# Compressor.net
KiCad netlist of a schematic drawn in EAGLE
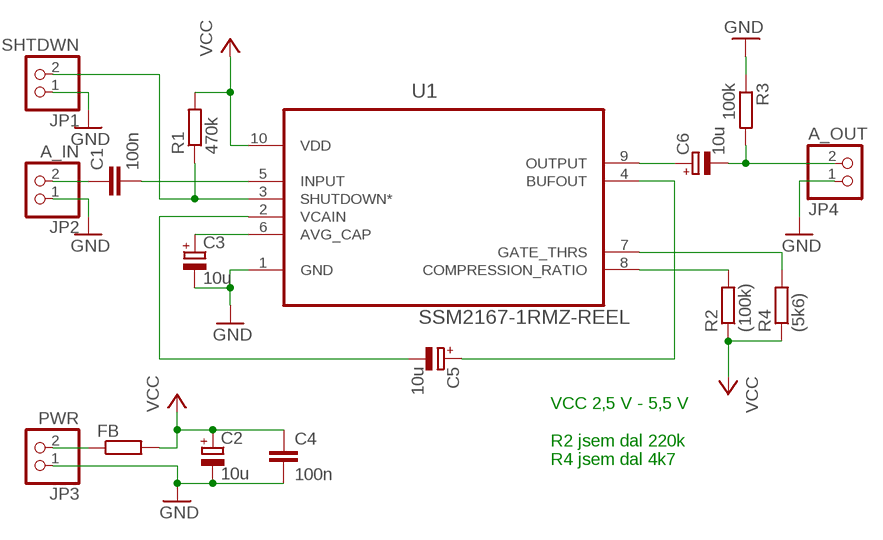
[diagram p0: schematic, sheet 1]

(export (version "E")
  (design (tool "Eeschema 10.0.6"))
  (components
    (comp (ref "C1")
      (value "100n")
      (footprint "eagle-import:C0603")
      (libsource (lib "eagle-import") (part "C-EUC0603"))
    )
    (comp (ref "C2")
      (value "10u")
      (footprint "eagle-import:SMC_A")
      (libsource (lib "eagle-import") (part "CPOL-EUSMCA"))
    )
    (comp (ref "C3")
      (value "10u")
      (footprint "eagle-import:SMC_A")
      (libsource (lib "eagle-import") (part "CPOL-EUSMCA"))
    )
    (comp (ref "C4")
      (value "100n")
      (footprint "eagle-import:C0603")
      (libsource (lib "eagle-import") (part "C-EUC0603"))
    )
    (comp (ref "C5")
      (value "10u")
      (footprint "eagle-import:SMC_A")
      (libsource (lib "eagle-import") (part "CPOL-EUSMCA"))
    )
    (comp (ref "C6")
      (value "10u")
      (footprint "eagle-import:SMC_A")
      (libsource (lib "eagle-import") (part "CPOL-EUSMCA"))
    )
    (comp (ref "FB")
      (value "R-EU_R0603")
      (footprint "eagle-import:R0603")
      (libsource (lib "eagle-import") (part "R-EU_R0603"))
    )
    (comp (ref "JP1")
      (value "SHTDWN")
      (footprint "eagle-import:1X02")
      (libsource (lib "eagle-import") (part "PINHD-1X2"))
    )
    (comp (ref "JP2")
      (value "A_IN")
      (footprint "eagle-import:1X02")
      (libsource (lib "eagle-import") (part "PINHD-1X2"))
    )
    (comp (ref "JP3")
      (value "PWR")
      (footprint "eagle-import:1X02")
      (libsource (lib "eagle-import") (part "PINHD-1X2"))
    )
    (comp (ref "JP4")
      (value "A_OUT")
      (footprint "eagle-import:1X02")
      (libsource (lib "eagle-import") (part "PINHD-1X2"))
    )
    (comp (ref "R1")
      (value "470k")
      (footprint "eagle-import:R0603")
      (libsource (lib "eagle-import") (part "R-EU_R0603"))
    )
    (comp (ref "R2")
      (value "(100k)")
      (footprint "eagle-import:R0603")
      (libsource (lib "eagle-import") (part "R-EU_R0603"))
    )
    (comp (ref "R3")
      (value "100k")
      (footprint "eagle-import:R0603")
      (libsource (lib "eagle-import") (part "R-EU_R0603"))
    )
    (comp (ref "R4")
      (value "(5k6)")
      (footprint "eagle-import:R0603")
      (libsource (lib "eagle-import") (part "R-EU_R0603"))
    )
    (comp (ref "U1")
      (value "SSM2167-1RMZ-REEL")
      (footprint "eagle-import:SOP50P490X110-10N")
      (libsource (lib "eagle-import") (part "SSM2167-1RMZ-REEL"))
    )
  )
  (nets
    (net (code "1") (name "GND") (class "Default")
      (node (ref "C2") (pin "-") (pinfunction "-_-") (pintype "passive"))
      (node (ref "C3") (pin "-") (pinfunction "-_-") (pintype "passive"))
      (node (ref "C4") (pin "2") (pinfunction "2_2") (pintype "passive"))
      (node (ref "JP1") (pin "1") (pinfunction "1_1") (pintype "passive"))
      (node (ref "JP2") (pin "1") (pinfunction "1_1") (pintype "passive"))
      (node (ref "JP3") (pin "1") (pinfunction "1_1") (pintype "passive"))
      (node (ref "JP4") (pin "1") (pinfunction "1_1") (pintype "passive"))
      (node (ref "R3") (pin "1") (pinfunction "1_1") (pintype "passive"))
      (node (ref "U1") (pin "1") (pinfunction "GND_1") (pintype "passive"))
    )
    (net (code "2") (name "Net-(C1-Pad1)") (class "Default")
      (node (ref "C1") (pin "1") (pinfunction "1_1") (pintype "passive"))
      (node (ref "JP2") (pin "2") (pinfunction "2_2") (pintype "passive"))
    )
    (net (code "3") (name "Net-(C6-Pad-)") (class "Default")
      (node (ref "C6") (pin "-") (pinfunction "-_-") (pintype "passive"))
      (node (ref "JP4") (pin "2") (pinfunction "2_2") (pintype "passive"))
      (node (ref "R3") (pin "2") (pinfunction "2_2") (pintype "passive"))
    )
    (net (code "4") (name "Net-(FB-Pad1)") (class "Default")
      (node (ref "FB") (pin "1") (pinfunction "1_1") (pintype "passive"))
      (node (ref "JP3") (pin "2") (pinfunction "2_2") (pintype "passive"))
    )
    (net (code "5") (name "Net-(U1-AVG_CAP)") (class "Default")
      (node (ref "C3") (pin "+") (pinfunction "+_+") (pintype "passive"))
      (node (ref "U1") (pin "6") (pinfunction "AVG_CAP_6") (pintype "passive"))
    )
    (net (code "6") (name "Net-(U1-BUFOUT)") (class "Default")
      (node (ref "C5") (pin "+") (pinfunction "+_+") (pintype "passive"))
      (node (ref "U1") (pin "4") (pinfunction "BUFOUT_4") (pintype "passive"))
    )
    (net (code "7") (name "Net-(U1-COMPRESSION_RATIO)") (class "Default")
      (node (ref "R2") (pin "2") (pinfunction "2_2") (pintype "passive"))
      (node (ref "U1") (pin "8") (pinfunction "COMPRESSION_RATIO_8") (pintype "passive"))
    )
    (net (code "8") (name "Net-(U1-GATE_THRS)") (class "Default")
      (node (ref "R4") (pin "2") (pinfunction "2_2") (pintype "passive"))
      (node (ref "U1") (pin "7") (pinfunction "GATE_THRS_7") (pintype "passive"))
    )
    (net (code "9") (name "Net-(U1-INPUT)") (class "Default")
      (node (ref "C1") (pin "2") (pinfunction "2_2") (pintype "passive"))
      (node (ref "U1") (pin "5") (pinfunction "INPUT_5") (pintype "passive"))
    )
    (net (code "10") (name "Net-(U1-OUTPUT)") (class "Default")
      (node (ref "C6") (pin "+") (pinfunction "+_+") (pintype "passive"))
      (node (ref "U1") (pin "9") (pinfunction "OUTPUT_9") (pintype "passive"))
    )
    (net (code "11") (name "Net-(U1-SHUTDOWN*)") (class "Default")
      (node (ref "JP1") (pin "2") (pinfunction "2_2") (pintype "passive"))
      (node (ref "R1") (pin "1") (pinfunction "1_1") (pintype "passive"))
      (node (ref "U1") (pin "3") (pinfunction "SHUTDOWN*_3") (pintype "passive"))
    )
    (net (code "12") (name "Net-(U1-VCAIN)") (class "Default")
      (node (ref "C5") (pin "-") (pinfunction "-_-") (pintype "passive"))
      (node (ref "U1") (pin "2") (pinfunction "VCAIN_2") (pintype "passive"))
    )
    (net (code "13") (name "VCC") (class "Default")
      (node (ref "C2") (pin "+") (pinfunction "+_+") (pintype "passive"))
      (node (ref "C4") (pin "1") (pinfunction "1_1") (pintype "passive"))
      (node (ref "FB") (pin "2") (pinfunction "2_2") (pintype "passive"))
      (node (ref "R1") (pin "2") (pinfunction "2_2") (pintype "passive"))
      (node (ref "R2") (pin "1") (pinfunction "1_1") (pintype "passive"))
      (node (ref "R4") (pin "1") (pinfunction "1_1") (pintype "passive"))
      (node (ref "U1") (pin "10") (pinfunction "VDD_10") (pintype "power_in"))
    )
  )
)
